# Ayrduino_v5_mint.net
KiCad netlist of a schematic drawn in EAGLE
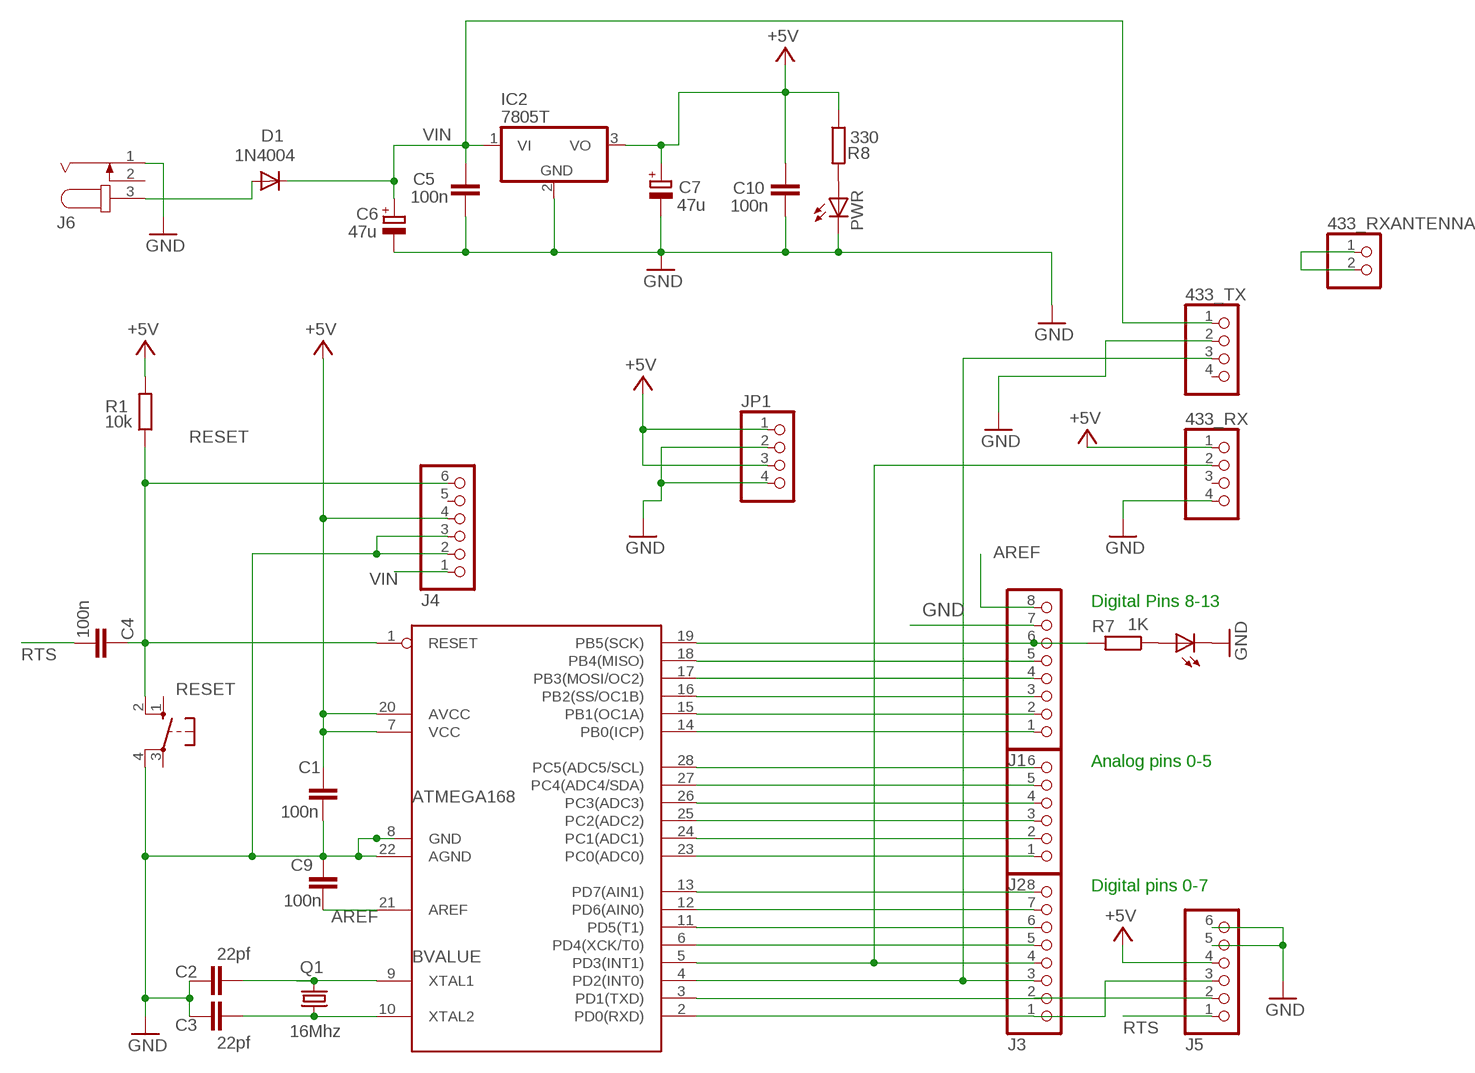
[diagram p0: schematic, sheet 1]

(export (version "E")
  (design (tool "Eeschema 10.0.6"))
  (components
    (comp (ref "433_RX")
      (value "PINHD-1X4")
      (footprint "eagle-import:1X04")
      (libsource (lib "eagle-import") (part "PINHD-1X4"))
    )
    (comp (ref "433_RXANTENNA")
      (value "PINHD-1X2")
      (footprint "eagle-import:1X02")
      (libsource (lib "eagle-import") (part "PINHD-1X2"))
    )
    (comp (ref "433_TX")
      (value "PINHD-1X4")
      (footprint "eagle-import:1X04")
      (libsource (lib "eagle-import") (part "PINHD-1X4"))
    )
    (comp (ref "BVALUE")
      (value "ATMEGA168")
      (footprint "eagle-import:DIL28-3")
      (libsource (lib "eagle-import") (part "MEGA8-P"))
    )
    (comp (ref "C1")
      (value "100n")
      (footprint "eagle-import:C050-024X044")
      (libsource (lib "eagle-import") (part "C-EU050-024X044"))
    )
    (comp (ref "C2")
      (value "22pf")
      (footprint "eagle-import:C025-024X044")
      (libsource (lib "eagle-import") (part "C-EU025-024X044"))
    )
    (comp (ref "C3")
      (value "22pf")
      (footprint "eagle-import:C025-024X044")
      (libsource (lib "eagle-import") (part "C-EU025-024X044"))
    )
    (comp (ref "C4")
      (value "100n")
      (footprint "eagle-import:C050-024X044")
      (libsource (lib "eagle-import") (part "C-EU050-024X044"))
    )
    (comp (ref "C5")
      (value "100n")
      (footprint "eagle-import:C050-024X044")
      (libsource (lib "eagle-import") (part "C-EU050-024X044"))
    )
    (comp (ref "C6")
      (value "47u")
      (footprint "eagle-import:E3,5-8")
      (libsource (lib "eagle-import") (part "CPOL-EUE3.5-8"))
    )
    (comp (ref "C7")
      (value "47u")
      (footprint "eagle-import:E3,5-8")
      (libsource (lib "eagle-import") (part "CPOL-EUE3.5-8"))
    )
    (comp (ref "C9")
      (value "100n")
      (footprint "eagle-import:C050-024X044")
      (libsource (lib "eagle-import") (part "C-EU050-024X044"))
    )
    (comp (ref "C10")
      (value "100n")
      (footprint "eagle-import:C050-024X044")
      (libsource (lib "eagle-import") (part "C-EU050-024X044"))
    )
    (comp (ref "D1")
      (value "1N4004")
      (footprint "eagle-import:DIODE-0.4")
      (libsource (lib "eagle-import") (part "DIODEPTH"))
    )
    (comp (ref "IC2")
      (value "7805T")
      (footprint "eagle-import:TO220H")
      (libsource (lib "eagle-import") (part "78T05"))
    )
    (comp (ref "J1")
      (value "PINHD-1X8")
      (footprint "eagle-import:1X08")
      (libsource (lib "eagle-import") (part "PINHD-1X8"))
    )
    (comp (ref "J2")
      (value "PINHD-1X6")
      (footprint "eagle-import:1X06")
      (libsource (lib "eagle-import") (part "PINHD-1X6"))
    )
    (comp (ref "J3")
      (value "PINHD-1X8")
      (footprint "eagle-import:1X08")
      (libsource (lib "eagle-import") (part "PINHD-1X8"))
    )
    (comp (ref "J4")
      (value "PINHD-1X6")
      (footprint "eagle-import:1X06")
      (libsource (lib "eagle-import") (part "PINHD-1X6"))
    )
    (comp (ref "J5")
      (value "PINHD-1X6")
      (footprint "eagle-import:1X06")
      (libsource (lib "eagle-import") (part "PINHD-1X6"))
    )
    (comp (ref "J6")
      (value "JACK-PLUG0")
      (footprint "eagle-import:SPC4077")
      (libsource (lib "eagle-import") (part "JACK-PLUG0"))
    )
    (comp (ref "JP1")
      (value "PINHD-1X4")
      (footprint "eagle-import:1X04")
      (libsource (lib "eagle-import") (part "PINHD-1X4"))
    )
    (comp (ref "P13")
      (value "LED3MM")
      (footprint "eagle-import:LED3MM")
      (libsource (lib "eagle-import") (part "LED3MM"))
    )
    (comp (ref "PWR")
      (value "LED3MM")
      (footprint "eagle-import:LED3MM")
      (libsource (lib "eagle-import") (part "LED3MM"))
    )
    (comp (ref "Q1")
      (value "16Mhz")
      (footprint "eagle-import:HC49U-V")
      (libsource (lib "eagle-import") (part "CRYSTALHC49U-V"))
    )
    (comp (ref "R1")
      (value "10k")
      (footprint "eagle-import:0204_7")
      (libsource (lib "eagle-import") (part "R-EU_0204/7"))
    )
    (comp (ref "R7")
      (value "1K")
      (footprint "eagle-import:0204_7")
      (libsource (lib "eagle-import") (part "R-EU_0204/7"))
    )
    (comp (ref "R8")
      (value "330")
      (footprint "eagle-import:0204_7")
      (libsource (lib "eagle-import") (part "R-EU_0204/7"))
    )
    (comp (ref "RESET")
      (value "10-XX")
      (footprint "eagle-import:B3F-10XX")
      (libsource (lib "eagle-import") (part "10-XX"))
    )
  )
  (nets
    (net (code "1") (name "+5V") (class "Default")
      (node (ref "433_RX") (pin "1") (pinfunction "1_1") (pintype "passive"))
      (node (ref "BVALUE") (pin "20") (pinfunction "AVCC_20") (pintype "bidirectional"))
      (node (ref "BVALUE") (pin "7") (pinfunction "VCC_7") (pintype "bidirectional"))
      (node (ref "C1") (pin "1") (pinfunction "1_1") (pintype "passive"))
      (node (ref "C10") (pin "2") (pinfunction "2_2") (pintype "passive"))
      (node (ref "C7") (pin "+") (pinfunction "+_+") (pintype "passive"))
      (node (ref "IC2") (pin "3") (pinfunction "VO_3") (pintype "passive"))
      (node (ref "J4") (pin "4") (pinfunction "4_4") (pintype "passive"))
      (node (ref "J5") (pin "4") (pinfunction "4_4") (pintype "passive"))
      (node (ref "JP1") (pin "1") (pinfunction "1_1") (pintype "passive"))
      (node (ref "JP1") (pin "3") (pinfunction "3_3") (pintype "passive"))
      (node (ref "R1") (pin "2") (pinfunction "2_2") (pintype "passive"))
      (node (ref "R8") (pin "1") (pinfunction "1_1") (pintype "passive"))
    )
    (net (code "2") (name "/AREF") (class "Default")
      (node (ref "BVALUE") (pin "21") (pinfunction "AREF_21") (pintype "bidirectional"))
      (node (ref "C9") (pin "1") (pinfunction "1_1") (pintype "passive"))
      (node (ref "J1") (pin "8") (pinfunction "8_8") (pintype "passive"))
    )
    (net (code "3") (name "/RESET") (class "Default")
      (node (ref "BVALUE") (pin "1") (pinfunction "RESET_1") (pintype "bidirectional"))
      (node (ref "C4") (pin "1") (pinfunction "1_1") (pintype "passive"))
      (node (ref "J4") (pin "6") (pinfunction "6_6") (pintype "passive"))
      (node (ref "R1") (pin "1") (pinfunction "1_1") (pintype "passive"))
      (node (ref "RESET") (pin "2") (pinfunction "S1_2") (pintype "passive"))
    )
    (net (code "4") (name "/RTS") (class "Default")
      (node (ref "C4") (pin "2") (pinfunction "2_2") (pintype "passive"))
      (node (ref "J5") (pin "1") (pinfunction "1_1") (pintype "passive"))
    )
    (net (code "5") (name "/VIN") (class "Default")
      (node (ref "433_TX") (pin "1") (pinfunction "1_1") (pintype "passive"))
      (node (ref "C5") (pin "2") (pinfunction "2_2") (pintype "passive"))
      (node (ref "C6") (pin "+") (pinfunction "+_+") (pintype "passive"))
      (node (ref "D1") (pin "C") (pinfunction "C_C") (pintype "passive"))
      (node (ref "IC2") (pin "1") (pinfunction "VI_1") (pintype "input"))
      (node (ref "J4") (pin "1") (pinfunction "1_1") (pintype "passive"))
    )
    (net (code "6") (name "GND") (class "Default")
      (node (ref "433_RX") (pin "4") (pinfunction "4_4") (pintype "passive"))
      (node (ref "433_TX") (pin "2") (pinfunction "2_2") (pintype "passive"))
      (node (ref "BVALUE") (pin "22") (pinfunction "AGND_22") (pintype "bidirectional"))
      (node (ref "BVALUE") (pin "8") (pinfunction "GND_8") (pintype "bidirectional"))
      (node (ref "C1") (pin "2") (pinfunction "2_2") (pintype "passive"))
      (node (ref "C10") (pin "1") (pinfunction "1_1") (pintype "passive"))
      (node (ref "C2") (pin "1") (pinfunction "1_1") (pintype "passive"))
      (node (ref "C3") (pin "1") (pinfunction "1_1") (pintype "passive"))
      (node (ref "C5") (pin "1") (pinfunction "1_1") (pintype "passive"))
      (node (ref "C6") (pin "-") (pinfunction "-_-") (pintype "passive"))
      (node (ref "C7") (pin "-") (pinfunction "-_-") (pintype "passive"))
      (node (ref "C9") (pin "2") (pinfunction "2_2") (pintype "passive"))
      (node (ref "IC2") (pin "2") (pinfunction "GND_2") (pintype "passive"))
      (node (ref "J1") (pin "7") (pinfunction "7_7") (pintype "passive"))
      (node (ref "J4") (pin "2") (pinfunction "2_2") (pintype "passive"))
      (node (ref "J4") (pin "3") (pinfunction "3_3") (pintype "passive"))
      (node (ref "J5") (pin "5") (pinfunction "5_5") (pintype "passive"))
      (node (ref "J5") (pin "6") (pinfunction "6_6") (pintype "passive"))
      (node (ref "J6") (pin "1") (pinfunction "1_1") (pintype "passive"))
      (node (ref "JP1") (pin "2") (pinfunction "2_2") (pintype "passive"))
      (node (ref "JP1") (pin "4") (pinfunction "4_4") (pintype "passive"))
      (node (ref "P13") (pin "K") (pinfunction "C_K") (pintype "passive"))
      (node (ref "PWR") (pin "K") (pinfunction "C_K") (pintype "passive"))
      (node (ref "RESET") (pin "4") (pinfunction "P1_4") (pintype "passive"))
    )
    (net (code "7") (name "Net-(433_RXANTENNA-Pad1)") (class "Default")
      (node (ref "433_RXANTENNA") (pin "1") (pinfunction "1_1") (pintype "passive"))
      (node (ref "433_RXANTENNA") (pin "2") (pinfunction "2_2") (pintype "passive"))
    )
    (net (code "8") (name "Net-(BVALUE-PB0(ICP))") (class "Default")
      (node (ref "BVALUE") (pin "14") (pinfunction "PB0(ICP)_14") (pintype "bidirectional"))
      (node (ref "J1") (pin "1") (pinfunction "1_1") (pintype "passive"))
    )
    (net (code "9") (name "Net-(BVALUE-PB1(OC1A))") (class "Default")
      (node (ref "BVALUE") (pin "15") (pinfunction "PB1(OC1A)_15") (pintype "bidirectional"))
      (node (ref "J1") (pin "2") (pinfunction "2_2") (pintype "passive"))
    )
    (net (code "10") (name "Net-(BVALUE-PB2(SS{slash}OC1B))") (class "Default")
      (node (ref "BVALUE") (pin "16") (pinfunction "PB2(SS/OC1B)_16") (pintype "bidirectional"))
      (node (ref "J1") (pin "3") (pinfunction "3_3") (pintype "passive"))
    )
    (net (code "11") (name "Net-(BVALUE-PB3(MOSI{slash}OC2))") (class "Default")
      (node (ref "BVALUE") (pin "17") (pinfunction "PB3(MOSI/OC2)_17") (pintype "bidirectional"))
      (node (ref "J1") (pin "4") (pinfunction "4_4") (pintype "passive"))
    )
    (net (code "12") (name "Net-(BVALUE-PB4(MISO))") (class "Default")
      (node (ref "BVALUE") (pin "18") (pinfunction "PB4(MISO)_18") (pintype "bidirectional"))
      (node (ref "J1") (pin "5") (pinfunction "5_5") (pintype "passive"))
    )
    (net (code "13") (name "Net-(BVALUE-PB5(SCK))") (class "Default")
      (node (ref "BVALUE") (pin "19") (pinfunction "PB5(SCK)_19") (pintype "bidirectional"))
      (node (ref "J1") (pin "6") (pinfunction "6_6") (pintype "passive"))
      (node (ref "R7") (pin "2") (pinfunction "2_2") (pintype "passive"))
    )
    (net (code "14") (name "Net-(BVALUE-PC0(ADC0))") (class "Default")
      (node (ref "BVALUE") (pin "23") (pinfunction "PC0(ADC0)_23") (pintype "bidirectional"))
      (node (ref "J2") (pin "1") (pinfunction "1_1") (pintype "passive"))
    )
    (net (code "15") (name "Net-(BVALUE-PC1(ADC1))") (class "Default")
      (node (ref "BVALUE") (pin "24") (pinfunction "PC1(ADC1)_24") (pintype "bidirectional"))
      (node (ref "J2") (pin "2") (pinfunction "2_2") (pintype "passive"))
    )
    (net (code "16") (name "Net-(BVALUE-PC2(ADC2))") (class "Default")
      (node (ref "BVALUE") (pin "25") (pinfunction "PC2(ADC2)_25") (pintype "bidirectional"))
      (node (ref "J2") (pin "3") (pinfunction "3_3") (pintype "passive"))
    )
    (net (code "17") (name "Net-(BVALUE-PC3(ADC3))") (class "Default")
      (node (ref "BVALUE") (pin "26") (pinfunction "PC3(ADC3)_26") (pintype "bidirectional"))
      (node (ref "J2") (pin "4") (pinfunction "4_4") (pintype "passive"))
    )
    (net (code "18") (name "Net-(BVALUE-PC4(ADC4{slash}SDA))") (class "Default")
      (node (ref "BVALUE") (pin "27") (pinfunction "PC4(ADC4/SDA)_27") (pintype "bidirectional"))
      (node (ref "J2") (pin "5") (pinfunction "5_5") (pintype "passive"))
    )
    (net (code "19") (name "Net-(BVALUE-PC5(ADC5{slash}SCL))") (class "Default")
      (node (ref "BVALUE") (pin "28") (pinfunction "PC5(ADC5/SCL)_28") (pintype "bidirectional"))
      (node (ref "J2") (pin "6") (pinfunction "6_6") (pintype "passive"))
    )
    (net (code "20") (name "Net-(BVALUE-PD0(RXD))") (class "Default")
      (node (ref "BVALUE") (pin "2") (pinfunction "PD0(RXD)_2") (pintype "bidirectional"))
      (node (ref "J3") (pin "1") (pinfunction "1_1") (pintype "passive"))
      (node (ref "J5") (pin "3") (pinfunction "3_3") (pintype "passive"))
    )
    (net (code "21") (name "Net-(BVALUE-PD1(TXD))") (class "Default")
      (node (ref "BVALUE") (pin "3") (pinfunction "PD1(TXD)_3") (pintype "bidirectional"))
      (node (ref "J3") (pin "2") (pinfunction "2_2") (pintype "passive"))
      (node (ref "J5") (pin "2") (pinfunction "2_2") (pintype "passive"))
    )
    (net (code "22") (name "Net-(BVALUE-PD2(INT0))") (class "Default")
      (node (ref "433_TX") (pin "3") (pinfunction "3_3") (pintype "passive"))
      (node (ref "BVALUE") (pin "4") (pinfunction "PD2(INT0)_4") (pintype "bidirectional"))
      (node (ref "J3") (pin "3") (pinfunction "3_3") (pintype "passive"))
    )
    (net (code "23") (name "Net-(BVALUE-PD3(INT1))") (class "Default")
      (node (ref "433_RX") (pin "2") (pinfunction "2_2") (pintype "passive"))
      (node (ref "BVALUE") (pin "5") (pinfunction "PD3(INT1)_5") (pintype "bidirectional"))
      (node (ref "J3") (pin "4") (pinfunction "4_4") (pintype "passive"))
    )
    (net (code "24") (name "Net-(BVALUE-PD4(XCK{slash}T0))") (class "Default")
      (node (ref "BVALUE") (pin "6") (pinfunction "PD4(XCK/T0)_6") (pintype "bidirectional"))
      (node (ref "J3") (pin "5") (pinfunction "5_5") (pintype "passive"))
    )
    (net (code "25") (name "Net-(BVALUE-PD5(T1))") (class "Default")
      (node (ref "BVALUE") (pin "11") (pinfunction "PD5(T1)_11") (pintype "bidirectional"))
      (node (ref "J3") (pin "6") (pinfunction "6_6") (pintype "passive"))
    )
    (net (code "26") (name "Net-(BVALUE-PD6(AIN0))") (class "Default")
      (node (ref "BVALUE") (pin "12") (pinfunction "PD6(AIN0)_12") (pintype "bidirectional"))
      (node (ref "J3") (pin "7") (pinfunction "7_7") (pintype "passive"))
    )
    (net (code "27") (name "Net-(BVALUE-PD7(AIN1))") (class "Default")
      (node (ref "BVALUE") (pin "13") (pinfunction "PD7(AIN1)_13") (pintype "bidirectional"))
      (node (ref "J3") (pin "8") (pinfunction "8_8") (pintype "passive"))
    )
    (net (code "28") (name "Net-(BVALUE-XTAL1)") (class "Default")
      (node (ref "BVALUE") (pin "9") (pinfunction "XTAL1_9") (pintype "bidirectional"))
      (node (ref "C2") (pin "2") (pinfunction "2_2") (pintype "passive"))
      (node (ref "Q1") (pin "2") (pinfunction "2_2") (pintype "passive"))
    )
    (net (code "29") (name "Net-(BVALUE-XTAL2)") (class "Default")
      (node (ref "BVALUE") (pin "10") (pinfunction "XTAL2_10") (pintype "bidirectional"))
      (node (ref "C3") (pin "2") (pinfunction "2_2") (pintype "passive"))
      (node (ref "Q1") (pin "1") (pinfunction "1_1") (pintype "passive"))
    )
    (net (code "30") (name "Net-(D1-PadA)") (class "Default")
      (node (ref "D1") (pin "A") (pinfunction "A_A") (pintype "passive"))
      (node (ref "J6") (pin "3") (pinfunction "3_3") (pintype "passive"))
    )
    (net (code "31") (name "Net-(P13-PadA)") (class "Default")
      (node (ref "P13") (pin "A") (pinfunction "A_A") (pintype "passive"))
      (node (ref "R7") (pin "1") (pinfunction "1_1") (pintype "passive"))
    )
    (net (code "32") (name "Net-(PWR-PadA)") (class "Default")
      (node (ref "PWR") (pin "A") (pinfunction "A_A") (pintype "passive"))
      (node (ref "R8") (pin "2") (pinfunction "2_2") (pintype "passive"))
    )
    (net (code "33") (name "unconnected-(433_RX-Pad3)") (class "Default")
      (node (ref "433_RX") (pin "3") (pinfunction "3_3") (pintype "passive"))
    )
    (net (code "34") (name "unconnected-(433_TX-Pad4)") (class "Default")
      (node (ref "433_TX") (pin "4") (pinfunction "4_4") (pintype "passive"))
    )
    (net (code "35") (name "unconnected-(J4-Pad5)") (class "Default")
      (node (ref "J4") (pin "5") (pinfunction "5_5") (pintype "passive"))
    )
    (net (code "36") (name "unconnected-(J6-Pad2)") (class "Default")
      (node (ref "J6") (pin "2") (pinfunction "2_2") (pintype "passive"))
    )
    (net (code "37") (name "unconnected-(RESET-P-Pad3)") (class "Default")
      (node (ref "RESET") (pin "3") (pinfunction "P_3") (pintype "passive"))
    )
    (net (code "38") (name "unconnected-(RESET-S-Pad1)") (class "Default")
      (node (ref "RESET") (pin "1") (pinfunction "S_1") (pintype "passive"))
    )
  )
)
